# Amp.net
KiCad netlist of a schematic drawn in EAGLE
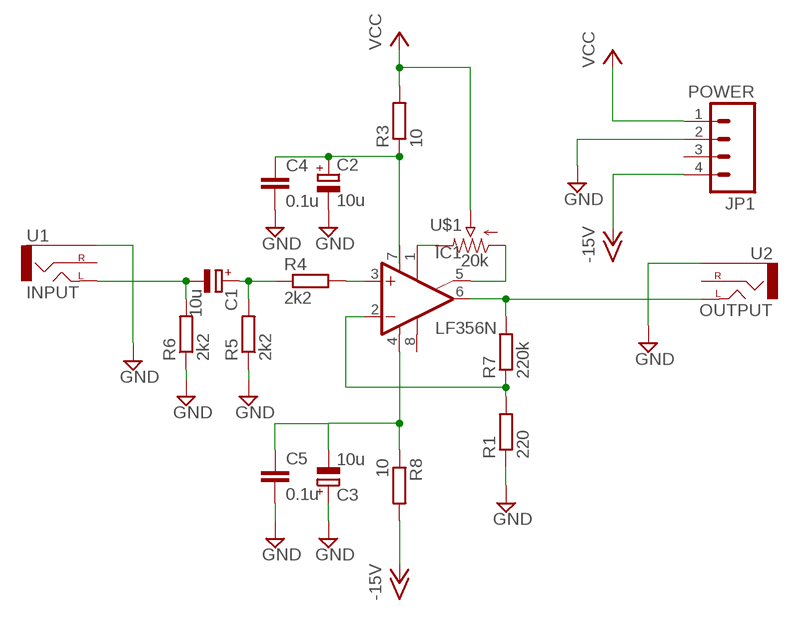
[diagram p0: schematic, sheet 1]

(export (version "E")
  (design (tool "Eeschema 10.0.6"))
  (components
    (comp (ref "C1")
      (value "10u")
      (footprint "eagle-import:E1,8-4")
      (libsource (lib "eagle-import") (part "CPOL-EUE1.8-4"))
    )
    (comp (ref "C2")
      (value "10u")
      (footprint "eagle-import:E1,8-4")
      (libsource (lib "eagle-import") (part "CPOL-EUE1.8-4"))
    )
    (comp (ref "C3")
      (value "10u")
      (footprint "eagle-import:E1,8-4")
      (libsource (lib "eagle-import") (part "CPOL-EUE1.8-4"))
    )
    (comp (ref "C4")
      (value "0.1u")
      (footprint "eagle-import:C025-024X044")
      (libsource (lib "eagle-import") (part "C-EU025-024X044"))
    )
    (comp (ref "C5")
      (value "0.1u")
      (footprint "eagle-import:C025-024X044")
      (libsource (lib "eagle-import") (part "C-EU025-024X044"))
    )
    (comp (ref "IC1")
      (value "LF356N")
      (footprint "eagle-import:DIL08")
      (libsource (lib "eagle-import") (part "LF356N"))
    )
    (comp (ref "JP1")
      (value "POWER")
      (footprint "eagle-import:MOLEX-1X4")
      (libsource (lib "eagle-import") (part "M04POLAR"))
    )
    (comp (ref "R1")
      (value "220")
      (footprint "eagle-import:0204_5")
      (libsource (lib "eagle-import") (part "R-EU_0204/5"))
    )
    (comp (ref "R3")
      (value "10")
      (footprint "eagle-import:0204_5")
      (libsource (lib "eagle-import") (part "R-EU_0204/5"))
    )
    (comp (ref "R4")
      (value "2k2")
      (footprint "eagle-import:0204_5")
      (libsource (lib "eagle-import") (part "R-EU_0204/5"))
    )
    (comp (ref "R5")
      (value "2k2")
      (footprint "eagle-import:0204_5")
      (libsource (lib "eagle-import") (part "R-EU_0204/5"))
    )
    (comp (ref "R6")
      (value "2k2")
      (footprint "eagle-import:0204_5")
      (libsource (lib "eagle-import") (part "R-EU_0204/5"))
    )
    (comp (ref "R7")
      (value "220k")
      (footprint "eagle-import:0204_5")
      (libsource (lib "eagle-import") (part "R-EU_0204/5"))
    )
    (comp (ref "R8")
      (value "10")
      (footprint "eagle-import:0204_5")
      (libsource (lib "eagle-import") (part "R-EU_0204/5"))
    )
    (comp (ref "U$1")
      (value "20k")
      (footprint "eagle-import:3362U")
      (libsource (lib "eagle-import") (part "POT100K_3362U"))
    )
    (comp (ref "U1")
      (value "INPUT")
      (footprint "eagle-import:STEREOJACK2.5MM_SPECIAL_HOLES-ONLY")
      (libsource (lib "eagle-import") (part "AUDIO-JACKHOLESONLY"))
    )
    (comp (ref "U2")
      (value "OUTPUT")
      (footprint "eagle-import:STEREOJACK2.5MM_SPECIAL_HOLES-ONLY")
      (libsource (lib "eagle-import") (part "AUDIO-JACKHOLESONLY"))
    )
  )
  (nets
    (net (code "1") (name "-15V") (class "Default")
      (node (ref "JP1") (pin "4") (pinfunction "4_4") (pintype "passive"))
      (node (ref "R8") (pin "2") (pinfunction "2_2") (pintype "passive"))
    )
    (net (code "2") (name "GND") (class "Default")
      (node (ref "C2") (pin "-") (pinfunction "-_-") (pintype "passive"))
      (node (ref "C3") (pin "+") (pinfunction "+_+") (pintype "passive"))
      (node (ref "C4") (pin "2") (pinfunction "2_2") (pintype "passive"))
      (node (ref "C5") (pin "2") (pinfunction "2_2") (pintype "passive"))
      (node (ref "JP1") (pin "2") (pinfunction "2_2") (pintype "passive"))
      (node (ref "R1") (pin "1") (pinfunction "1_1") (pintype "passive"))
      (node (ref "R5") (pin "1") (pinfunction "1_1") (pintype "passive"))
      (node (ref "R6") (pin "1") (pinfunction "1_1") (pintype "passive"))
      (node (ref "U1") (pin "RING1") (pinfunction "SLEEVE_RING1") (pintype "bidirectional"))
      (node (ref "U2") (pin "RING1") (pinfunction "SLEEVE_RING1") (pintype "bidirectional"))
    )
    (net (code "3") (name "Net-(C1-Pad+)") (class "Default")
      (node (ref "C1") (pin "+") (pinfunction "+_+") (pintype "passive"))
      (node (ref "R4") (pin "1") (pinfunction "1_1") (pintype "passive"))
      (node (ref "R5") (pin "2") (pinfunction "2_2") (pintype "passive"))
    )
    (net (code "4") (name "Net-(IC1-+IN)") (class "Default")
      (node (ref "IC1") (pin "3") (pinfunction "+IN_3") (pintype "input"))
      (node (ref "R4") (pin "2") (pinfunction "2_2") (pintype "passive"))
    )
    (net (code "5") (name "Net-(IC1--IN)") (class "Default")
      (node (ref "IC1") (pin "2") (pinfunction "-IN_2") (pintype "input"))
      (node (ref "R1") (pin "2") (pinfunction "2_2") (pintype "passive"))
      (node (ref "R7") (pin "1") (pinfunction "1_1") (pintype "passive"))
    )
    (net (code "6") (name "Net-(IC1-ON1)") (class "Default")
      (node (ref "IC1") (pin "1") (pinfunction "ON1_1") (pintype "passive"))
      (node (ref "U$1") (pin "P$1") (pinfunction "E_P$1") (pintype "passive"))
    )
    (net (code "7") (name "Net-(IC1-ON2)") (class "Default")
      (node (ref "IC1") (pin "5") (pinfunction "ON2_5") (pintype "passive"))
      (node (ref "U$1") (pin "P$3") (pinfunction "A_P$3") (pintype "passive"))
    )
    (net (code "8") (name "Net-(IC1-OUT)") (class "Default")
      (node (ref "IC1") (pin "6") (pinfunction "OUT_6") (pintype "output"))
      (node (ref "R7") (pin "2") (pinfunction "2_2") (pintype "passive"))
      (node (ref "U2") (pin "SHIELD") (pinfunction "LEFT_SHIELD") (pintype "bidirectional"))
    )
    (net (code "9") (name "Net-(IC1-V+)") (class "Default")
      (node (ref "C2") (pin "+") (pinfunction "+_+") (pintype "passive"))
      (node (ref "C4") (pin "1") (pinfunction "1_1") (pintype "passive"))
      (node (ref "IC1") (pin "7") (pinfunction "V+_7") (pintype "power_in"))
      (node (ref "R3") (pin "1") (pinfunction "1_1") (pintype "passive"))
    )
    (net (code "10") (name "Net-(IC1-V-)") (class "Default")
      (node (ref "C3") (pin "-") (pinfunction "-_-") (pintype "passive"))
      (node (ref "C5") (pin "1") (pinfunction "1_1") (pintype "passive"))
      (node (ref "IC1") (pin "4") (pinfunction "V-_4") (pintype "power_in"))
      (node (ref "R8") (pin "1") (pinfunction "1_1") (pintype "passive"))
    )
    (net (code "11") (name "Net-(U1-LEFT)") (class "Default")
      (node (ref "C1") (pin "-") (pinfunction "-_-") (pintype "passive"))
      (node (ref "R6") (pin "2") (pinfunction "2_2") (pintype "passive"))
      (node (ref "U1") (pin "SHIELD") (pinfunction "LEFT_SHIELD") (pintype "bidirectional"))
    )
    (net (code "12") (name "VCC") (class "Default")
      (node (ref "JP1") (pin "1") (pinfunction "1_1") (pintype "passive"))
      (node (ref "R3") (pin "2") (pinfunction "2_2") (pintype "passive"))
      (node (ref "U$1") (pin "P$2") (pinfunction "S_P$2") (pintype "passive"))
    )
    (net (code "13") (name "unconnected-(IC1-OPT-Pad8)") (class "Default")
      (node (ref "IC1") (pin "8") (pinfunction "OPT_8") (pintype "passive"))
    )
    (net (code "14") (name "unconnected-(JP1-Pad3)") (class "Default")
      (node (ref "JP1") (pin "3") (pinfunction "3_3") (pintype "passive"))
    )
    (net (code "15") (name "unconnected-(U1-RIGHT-PadTIP)") (class "Default")
      (node (ref "U1") (pin "TIP") (pinfunction "RIGHT_TIP") (pintype "bidirectional"))
    )
    (net (code "16") (name "unconnected-(U2-RIGHT-PadTIP)") (class "Default")
      (node (ref "U2") (pin "TIP") (pinfunction "RIGHT_TIP") (pintype "bidirectional"))
    )
  )
)
